# TKeyboard_2021-06-10.net
KiCad netlist of a schematic drawn in Altium Designer
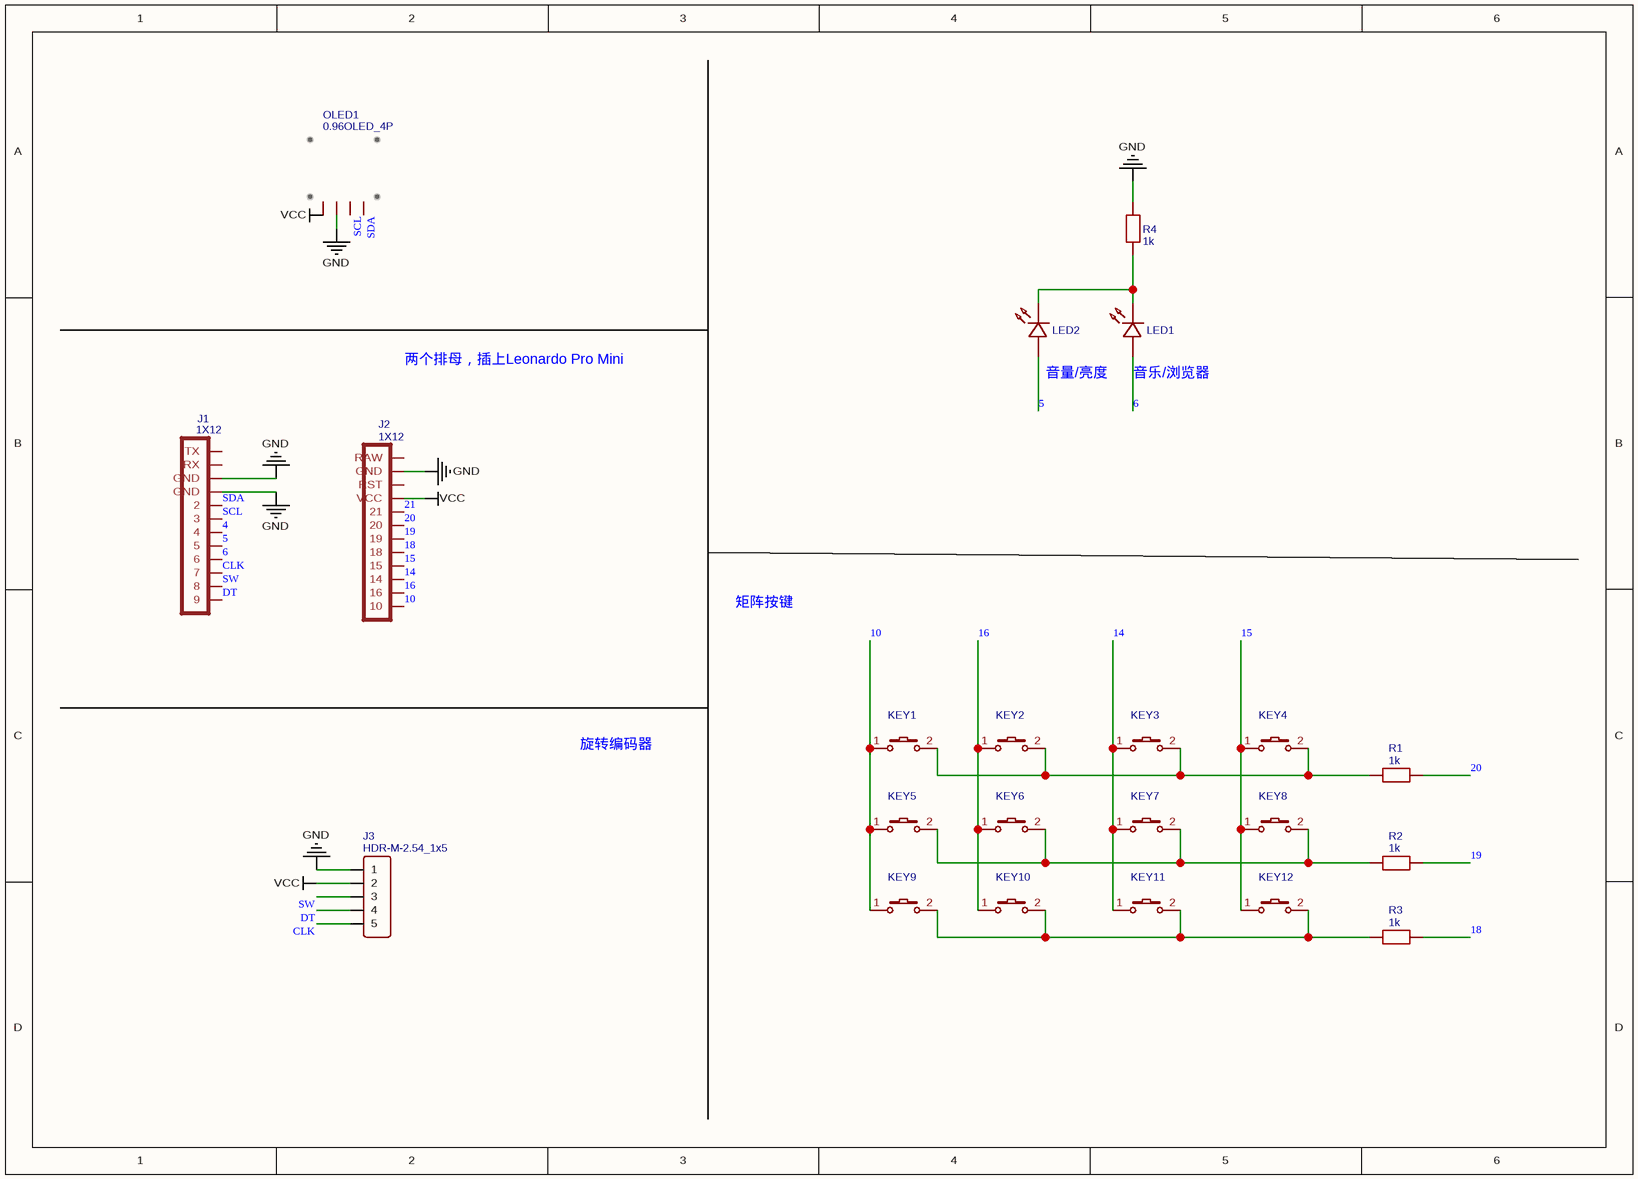
[diagram p0: TKeyboard_2021-06-10.schdoc]

(export (version "E")
  (design (tool "Eeschema 10.0.6"))
  (components
    (comp (ref "J1") (value "1X12") (libsource (lib "altium-import") (part "root_0_1X12_")))
    (comp (ref "J2") (value "1X12") (libsource (lib "altium-import") (part "root_0_1X12_")))
    (comp (ref "J3")
      (value "HDR-M-2.54_1x5")
      (fields (field (name "BOM_SUPPLIER PART") "C358687") (field (name "CONTRIBUTOR") "LCEDA_Lib"))
      (libsource (lib "altium-import") (part "root_0_HDR-M-2.54_1x5_"))
    )
    (comp (ref "KEY1")
      (value "K2-3.6×6.1_SMD")
      (fields
        (field (name "BOM_SUPPLIER PART") "C118141")
        (field (name "BOM_MANUFACTURER PART") "K2-1107ST-A4SW-06")
        (field (name "CONTRIBUTOR") "LCEDA_Lib")
      )
      (libsource (lib "altium-import") (part "root_0_K2-3.6×6.1_SMD_"))
    )
    (comp (ref "KEY2")
      (value "K2-3.6×6.1_SMD")
      (fields
        (field (name "BOM_SUPPLIER PART") "C118141")
        (field (name "BOM_MANUFACTURER PART") "K2-1107ST-A4SW-06")
        (field (name "CONTRIBUTOR") "LCEDA_Lib")
      )
      (libsource (lib "altium-import") (part "root_0_K2-3.6×6.1_SMD_"))
    )
    (comp (ref "KEY3")
      (value "K2-3.6×6.1_SMD")
      (fields
        (field (name "BOM_SUPPLIER PART") "C118141")
        (field (name "BOM_MANUFACTURER PART") "K2-1107ST-A4SW-06")
        (field (name "CONTRIBUTOR") "LCEDA_Lib")
      )
      (libsource (lib "altium-import") (part "root_0_K2-3.6×6.1_SMD_"))
    )
    (comp (ref "KEY4")
      (value "K2-3.6×6.1_SMD")
      (fields
        (field (name "BOM_SUPPLIER PART") "C118141")
        (field (name "BOM_MANUFACTURER PART") "K2-1107ST-A4SW-06")
        (field (name "CONTRIBUTOR") "LCEDA_Lib")
      )
      (libsource (lib "altium-import") (part "root_0_K2-3.6×6.1_SMD_"))
    )
    (comp (ref "KEY5")
      (value "K2-3.6×6.1_SMD")
      (fields
        (field (name "BOM_SUPPLIER PART") "C118141")
        (field (name "BOM_MANUFACTURER PART") "K2-1107ST-A4SW-06")
        (field (name "CONTRIBUTOR") "LCEDA_Lib")
      )
      (libsource (lib "altium-import") (part "root_0_K2-3.6×6.1_SMD_"))
    )
    (comp (ref "KEY6")
      (value "K2-3.6×6.1_SMD")
      (fields
        (field (name "BOM_SUPPLIER PART") "C118141")
        (field (name "BOM_MANUFACTURER PART") "K2-1107ST-A4SW-06")
        (field (name "CONTRIBUTOR") "LCEDA_Lib")
      )
      (libsource (lib "altium-import") (part "root_0_K2-3.6×6.1_SMD_"))
    )
    (comp (ref "KEY7")
      (value "K2-3.6×6.1_SMD")
      (fields
        (field (name "BOM_SUPPLIER PART") "C118141")
        (field (name "BOM_MANUFACTURER PART") "K2-1107ST-A4SW-06")
        (field (name "CONTRIBUTOR") "LCEDA_Lib")
      )
      (libsource (lib "altium-import") (part "root_0_K2-3.6×6.1_SMD_"))
    )
    (comp (ref "KEY8")
      (value "K2-3.6×6.1_SMD")
      (fields
        (field (name "BOM_SUPPLIER PART") "C118141")
        (field (name "BOM_MANUFACTURER PART") "K2-1107ST-A4SW-06")
        (field (name "CONTRIBUTOR") "LCEDA_Lib")
      )
      (libsource (lib "altium-import") (part "root_0_K2-3.6×6.1_SMD_"))
    )
    (comp (ref "KEY9")
      (value "K2-3.6×6.1_SMD")
      (fields
        (field (name "BOM_SUPPLIER PART") "C118141")
        (field (name "BOM_MANUFACTURER PART") "K2-1107ST-A4SW-06")
        (field (name "CONTRIBUTOR") "LCEDA_Lib")
      )
      (libsource (lib "altium-import") (part "root_0_K2-3.6×6.1_SMD_"))
    )
    (comp (ref "KEY10")
      (value "K2-3.6×6.1_SMD")
      (fields
        (field (name "BOM_SUPPLIER PART") "C118141")
        (field (name "BOM_MANUFACTURER PART") "K2-1107ST-A4SW-06")
        (field (name "CONTRIBUTOR") "LCEDA_Lib")
      )
      (libsource (lib "altium-import") (part "root_0_K2-3.6×6.1_SMD_"))
    )
    (comp (ref "KEY11")
      (value "K2-3.6×6.1_SMD")
      (fields
        (field (name "BOM_SUPPLIER PART") "C118141")
        (field (name "BOM_MANUFACTURER PART") "K2-1107ST-A4SW-06")
        (field (name "CONTRIBUTOR") "LCEDA_Lib")
      )
      (libsource (lib "altium-import") (part "root_0_K2-3.6×6.1_SMD_"))
    )
    (comp (ref "KEY12")
      (value "K2-3.6×6.1_SMD")
      (fields
        (field (name "BOM_SUPPLIER PART") "C118141")
        (field (name "BOM_MANUFACTURER PART") "K2-1107ST-A4SW-06")
        (field (name "CONTRIBUTOR") "LCEDA_Lib")
      )
      (libsource (lib "altium-import") (part "root_0_K2-3.6×6.1_SMD_"))
    )
    (comp (ref "LED1")
      (value "LED-0603_R")
      (fields
        (field (name "BOM_MANUFACTURER PART") "19-217/R6C-AL1M2VY/3T")
        (field (name "BOM_SUPPLIER PART") "C72044")
        (field (name "CONTRIBUTOR") "LCEDA_01")
      )
      (libsource (lib "altium-import") (part "root_1_LED-0603_R_"))
    )
    (comp (ref "LED2")
      (value "LED-0603_R")
      (fields
        (field (name "BOM_MANUFACTURER PART") "19-217/R6C-AL1M2VY/3T")
        (field (name "BOM_SUPPLIER PART") "C72044")
        (field (name "CONTRIBUTOR") "LCEDA_01")
      )
      (libsource (lib "altium-import") (part "root_1_LED-0603_R_"))
    )
    (comp (ref "OLED1")
      (value "0.96OLED_4P")
      (fields (field (name "CONTRIBUTOR") "LCEDA_Lib"))
      (libsource (lib "altium-import") (part "root_0_0.96OLED_4P_"))
    )
    (comp (ref "R1")
      (value "1k")
      (fields (field (name "CONTRIBUTOR") "LCEDA_Lib"))
      (libsource (lib "altium-import") (part "root_0_1k_"))
    )
    (comp (ref "R2")
      (value "1k")
      (fields (field (name "CONTRIBUTOR") "LCEDA_Lib"))
      (libsource (lib "altium-import") (part "root_0_1k_"))
    )
    (comp (ref "R3")
      (value "1k")
      (fields (field (name "CONTRIBUTOR") "LCEDA_Lib"))
      (libsource (lib "altium-import") (part "root_0_1k_"))
    )
    (comp (ref "R4")
      (value "1k")
      (fields (field (name "CONTRIBUTOR") "LCEDA_Lib"))
      (libsource (lib "altium-import") (part "root_1_1k_"))
    )
  )
  (nets
    (net (code "1") (name "/4") (class "Default")
      (node (ref "J1") (pin "6") (pinfunction "4_6") (pintype "passive"))
    )
    (net (code "2") (name "/5") (class "Default")
      (node (ref "J1") (pin "5") (pinfunction "5_5") (pintype "passive"))
      (node (ref "LED2") (pin "1") (pinfunction "1_1") (pintype "passive"))
    )
    (net (code "3") (name "/6") (class "Default")
      (node (ref "J1") (pin "4") (pinfunction "6_4") (pintype "passive"))
      (node (ref "LED1") (pin "1") (pinfunction "1_1") (pintype "passive"))
    )
    (net (code "4") (name "/10") (class "Default")
      (node (ref "J2") (pin "1") (pinfunction "9_1") (pintype "passive"))
      (node (ref "KEY1") (pin "1") (pinfunction "1_1") (pintype "passive"))
      (node (ref "KEY5") (pin "1") (pinfunction "1_1") (pintype "passive"))
      (node (ref "KEY9") (pin "1") (pinfunction "1_1") (pintype "passive"))
    )
    (net (code "5") (name "/14") (class "Default")
      (node (ref "J2") (pin "3") (pinfunction "7_3") (pintype "passive"))
      (node (ref "KEY11") (pin "1") (pinfunction "1_1") (pintype "passive"))
      (node (ref "KEY3") (pin "1") (pinfunction "1_1") (pintype "passive"))
      (node (ref "KEY7") (pin "1") (pinfunction "1_1") (pintype "passive"))
    )
    (net (code "6") (name "/15") (class "Default")
      (node (ref "J2") (pin "4") (pinfunction "6_4") (pintype "passive"))
      (node (ref "KEY12") (pin "1") (pinfunction "1_1") (pintype "passive"))
      (node (ref "KEY4") (pin "1") (pinfunction "1_1") (pintype "passive"))
      (node (ref "KEY8") (pin "1") (pinfunction "1_1") (pintype "passive"))
    )
    (net (code "7") (name "/16") (class "Default")
      (node (ref "J2") (pin "2") (pinfunction "8_2") (pintype "passive"))
      (node (ref "KEY10") (pin "1") (pinfunction "1_1") (pintype "passive"))
      (node (ref "KEY2") (pin "1") (pinfunction "1_1") (pintype "passive"))
      (node (ref "KEY6") (pin "1") (pinfunction "1_1") (pintype "passive"))
    )
    (net (code "8") (name "/18") (class "Default")
      (node (ref "J2") (pin "5") (pinfunction "5_5") (pintype "passive"))
      (node (ref "R3") (pin "2") (pinfunction "2_2") (pintype "passive"))
    )
    (net (code "9") (name "/19") (class "Default")
      (node (ref "J2") (pin "6") (pinfunction "4_6") (pintype "passive"))
      (node (ref "R2") (pin "2") (pinfunction "2_2") (pintype "passive"))
    )
    (net (code "10") (name "/20") (class "Default")
      (node (ref "J2") (pin "7") (pinfunction "3_7") (pintype "passive"))
      (node (ref "R1") (pin "2") (pinfunction "2_2") (pintype "passive"))
    )
    (net (code "11") (name "/21") (class "Default")
      (node (ref "J2") (pin "8") (pinfunction "2_8") (pintype "passive"))
    )
    (net (code "12") (name "/CLK") (class "Default")
      (node (ref "J1") (pin "3") (pinfunction "7_3") (pintype "passive"))
      (node (ref "J3") (pin "5") (pinfunction "5_5") (pintype "passive"))
    )
    (net (code "13") (name "/DT") (class "Default")
      (node (ref "J1") (pin "1") (pinfunction "9_1") (pintype "passive"))
      (node (ref "J3") (pin "4") (pinfunction "4_4") (pintype "passive"))
    )
    (net (code "14") (name "/SCL") (class "Default")
      (node (ref "J1") (pin "7") (pinfunction "3_7") (pintype "passive"))
      (node (ref "OLED1") (pin "3") (pinfunction "3_3") (pintype "passive"))
    )
    (net (code "15") (name "/SDA") (class "Default")
      (node (ref "J1") (pin "8") (pinfunction "2_8") (pintype "passive"))
      (node (ref "OLED1") (pin "4") (pinfunction "4_4") (pintype "passive"))
    )
    (net (code "16") (name "/SW") (class "Default")
      (node (ref "J1") (pin "2") (pinfunction "8_2") (pintype "passive"))
      (node (ref "J3") (pin "3") (pinfunction "3_3") (pintype "passive"))
    )
    (net (code "17") (name "GND") (class "Default")
      (node (ref "J1") (pin "10") (pinfunction "GND_10") (pintype "passive"))
      (node (ref "J1") (pin "9") (pinfunction "GND_9") (pintype "passive"))
      (node (ref "J2") (pin "11") (pinfunction "RX_11") (pintype "passive"))
      (node (ref "J3") (pin "1") (pinfunction "1_1") (pintype "passive"))
      (node (ref "OLED1") (pin "2") (pinfunction "2_2") (pintype "passive"))
      (node (ref "R4") (pin "2") (pinfunction "2_2") (pintype "passive"))
    )
    (net (code "18") (name "Net-(KEY1-Pad2)") (class "Default")
      (node (ref "KEY1") (pin "2") (pinfunction "2_2") (pintype "passive"))
      (node (ref "KEY2") (pin "2") (pinfunction "2_2") (pintype "passive"))
      (node (ref "KEY3") (pin "2") (pinfunction "2_2") (pintype "passive"))
      (node (ref "KEY4") (pin "2") (pinfunction "2_2") (pintype "passive"))
      (node (ref "R1") (pin "1") (pinfunction "1_1") (pintype "passive"))
    )
    (net (code "19") (name "Net-(KEY5-Pad2)") (class "Default")
      (node (ref "KEY5") (pin "2") (pinfunction "2_2") (pintype "passive"))
      (node (ref "KEY6") (pin "2") (pinfunction "2_2") (pintype "passive"))
      (node (ref "KEY7") (pin "2") (pinfunction "2_2") (pintype "passive"))
      (node (ref "KEY8") (pin "2") (pinfunction "2_2") (pintype "passive"))
      (node (ref "R2") (pin "1") (pinfunction "1_1") (pintype "passive"))
    )
    (net (code "20") (name "Net-(KEY10-Pad2)") (class "Default")
      (node (ref "KEY10") (pin "2") (pinfunction "2_2") (pintype "passive"))
      (node (ref "KEY11") (pin "2") (pinfunction "2_2") (pintype "passive"))
      (node (ref "KEY12") (pin "2") (pinfunction "2_2") (pintype "passive"))
      (node (ref "KEY9") (pin "2") (pinfunction "2_2") (pintype "passive"))
      (node (ref "R3") (pin "1") (pinfunction "1_1") (pintype "passive"))
    )
    (net (code "21") (name "Net-(LED1-Pad2)") (class "Default")
      (node (ref "LED1") (pin "2") (pinfunction "2_2") (pintype "passive"))
      (node (ref "LED2") (pin "2") (pinfunction "2_2") (pintype "passive"))
      (node (ref "R4") (pin "1") (pinfunction "1_1") (pintype "passive"))
    )
    (net (code "22") (name "VCC") (class "Default")
      (node (ref "J2") (pin "9") (pinfunction "GND_9") (pintype "passive"))
      (node (ref "J3") (pin "2") (pinfunction "2_2") (pintype "passive"))
      (node (ref "OLED1") (pin "1") (pinfunction "1_1") (pintype "passive"))
    )
    (net (code "23") (name "unconnected-(J1-RX-Pad11)") (class "Default")
      (node (ref "J1") (pin "11") (pinfunction "RX_11") (pintype "passive"))
    )
    (net (code "24") (name "unconnected-(J1-TX-Pad12)") (class "Default")
      (node (ref "J1") (pin "12") (pinfunction "TX_12") (pintype "passive"))
    )
    (net (code "25") (name "unconnected-(J2-GND-Pad10)") (class "Default")
      (node (ref "J2") (pin "10") (pinfunction "GND_10") (pintype "passive"))
    )
    (net (code "26") (name "unconnected-(J2-TX-Pad12)") (class "Default")
      (node (ref "J2") (pin "12") (pinfunction "TX_12") (pintype "passive"))
    )
  )
)
